# ADC.net
KiCad netlist of a schematic drawn in EAGLE
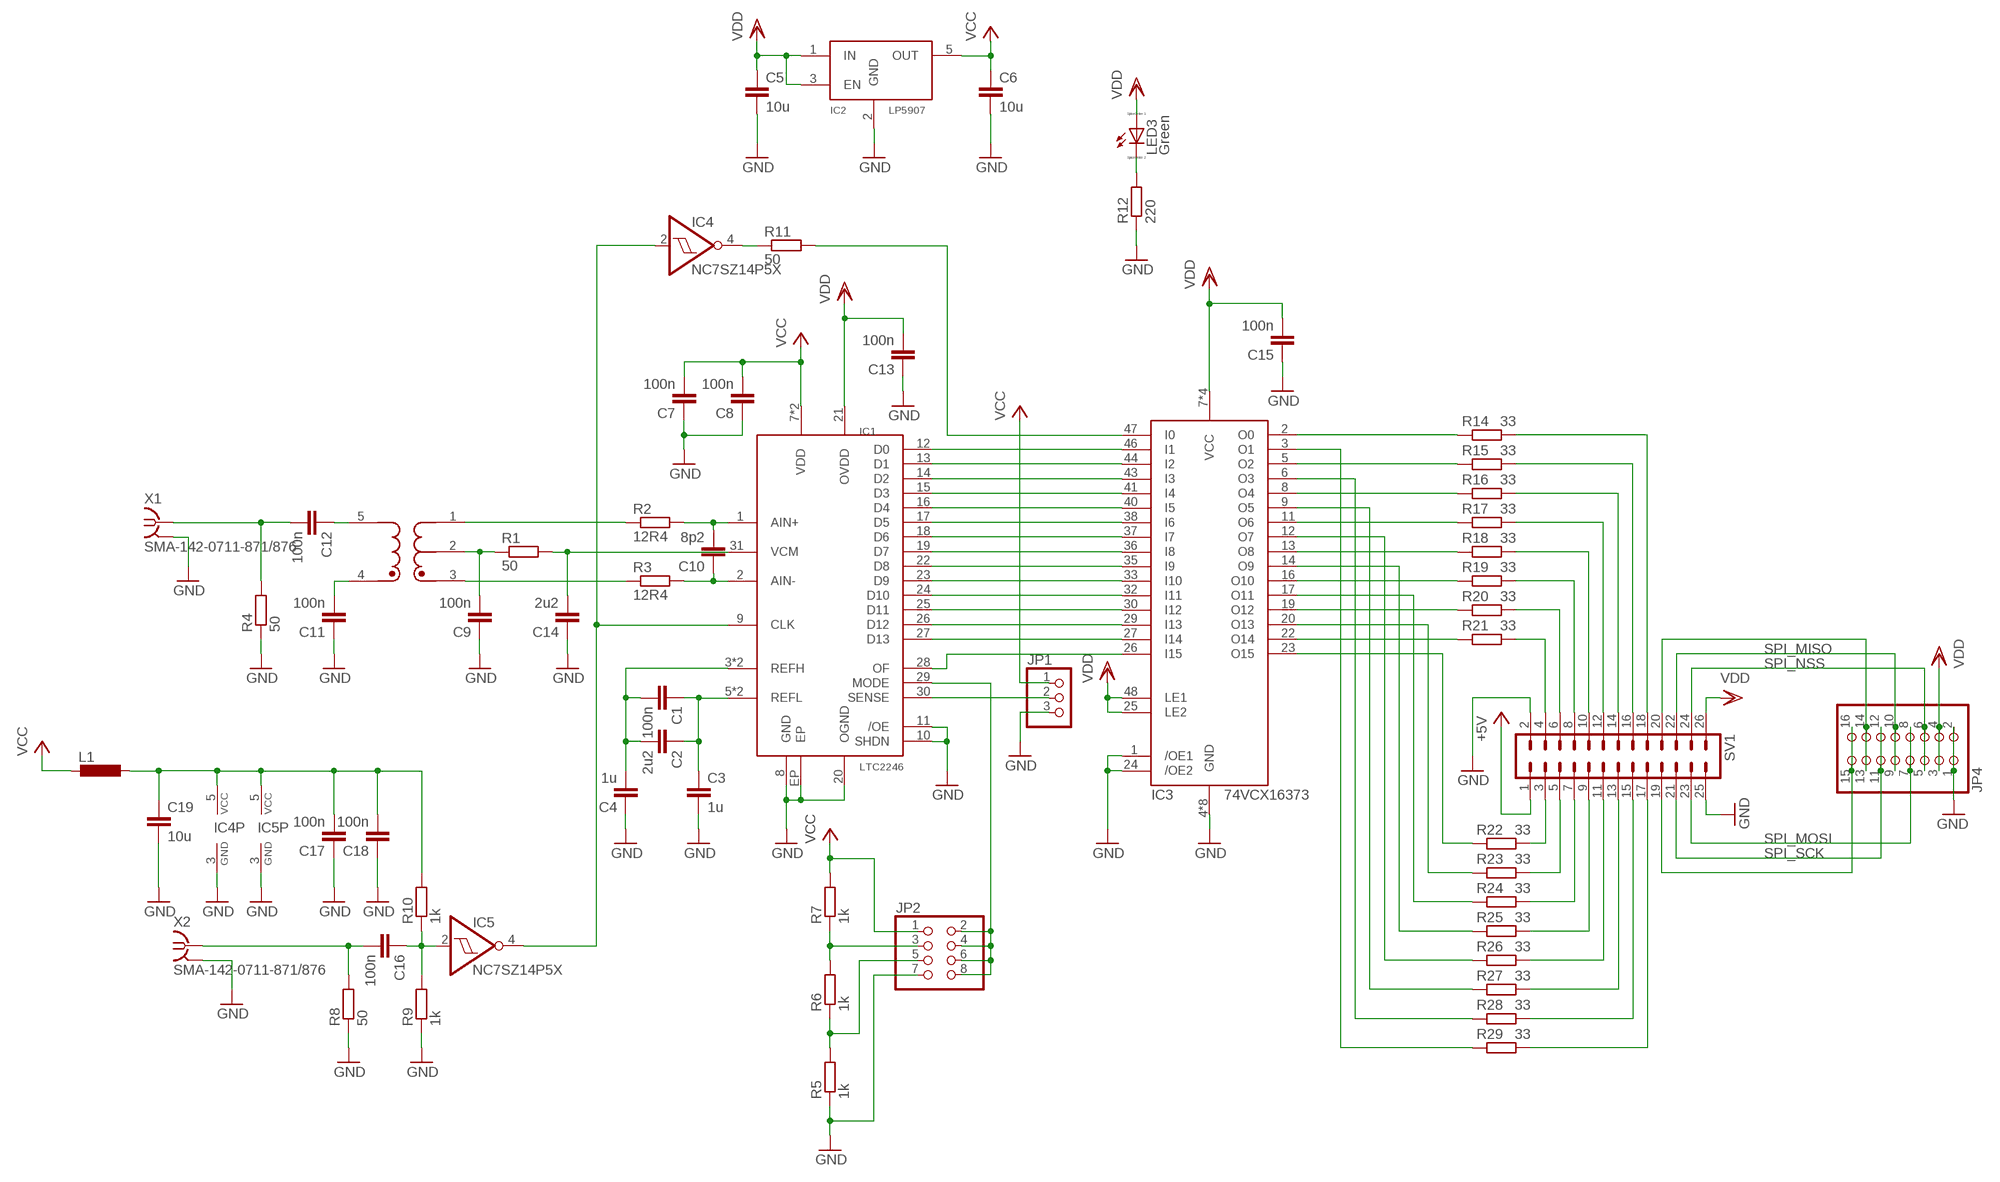
[diagram p0: schematic, sheet 1]

(export (version "E")
  (design (tool "Eeschema 10.0.6"))
  (components
    (comp (ref "B1")
      (value "ETC1-1T")
      (footprint "eagle-import:SM-22")
      (libsource (lib "eagle-import") (part "ETC1-1T"))
    )
    (comp (ref "C1")
      (value "100n")
      (footprint "eagle-import:C0402K")
      (libsource (lib "eagle-import") (part "C-EUC0402K"))
    )
    (comp (ref "C2")
      (value "2u2")
      (footprint "eagle-import:C0603K")
      (libsource (lib "eagle-import") (part "C-EUC0603K"))
    )
    (comp (ref "C3")
      (value "1u")
      (footprint "eagle-import:C0603K")
      (libsource (lib "eagle-import") (part "C-EUC0603K"))
    )
    (comp (ref "C4")
      (value "1u")
      (footprint "eagle-import:C0603K")
      (libsource (lib "eagle-import") (part "C-EUC0603K"))
    )
    (comp (ref "C5")
      (value "10u")
      (footprint "eagle-import:C1206K")
      (libsource (lib "eagle-import") (part "resistor_C-EUC1206K"))
    )
    (comp (ref "C6")
      (value "10u")
      (footprint "eagle-import:C1206K")
      (libsource (lib "eagle-import") (part "resistor_C-EUC1206K"))
    )
    (comp (ref "C7")
      (value "100n")
      (footprint "eagle-import:C0603K")
      (libsource (lib "eagle-import") (part "C-EUC0603K"))
    )
    (comp (ref "C8")
      (value "100n")
      (footprint "eagle-import:C0603K")
      (libsource (lib "eagle-import") (part "C-EUC0603K"))
    )
    (comp (ref "C9")
      (value "100n")
      (footprint "eagle-import:C0603K")
      (libsource (lib "eagle-import") (part "C-EUC0603K"))
    )
    (comp (ref "C10")
      (value "8p2")
      (footprint "eagle-import:C0603K")
      (libsource (lib "eagle-import") (part "C-EUC0603K"))
    )
    (comp (ref "C11")
      (value "100n")
      (footprint "eagle-import:C0603K")
      (libsource (lib "eagle-import") (part "C-EUC0603K"))
    )
    (comp (ref "C12")
      (value "100n")
      (footprint "eagle-import:C0603K")
      (libsource (lib "eagle-import") (part "C-EUC0603K"))
    )
    (comp (ref "C13")
      (value "100n")
      (footprint "eagle-import:C0402K")
      (libsource (lib "eagle-import") (part "C-EUC0402K"))
    )
    (comp (ref "C14")
      (value "2u2")
      (footprint "eagle-import:C0603K")
      (libsource (lib "eagle-import") (part "C-EUC0603K"))
    )
    (comp (ref "C15")
      (value "100n")
      (footprint "eagle-import:C0603K")
      (libsource (lib "eagle-import") (part "C-EUC0603K"))
    )
    (comp (ref "C16")
      (value "100n")
      (footprint "eagle-import:C0603K")
      (libsource (lib "eagle-import") (part "C-EUC0603K"))
    )
    (comp (ref "C17")
      (value "100n")
      (footprint "eagle-import:C0603K")
      (libsource (lib "eagle-import") (part "C-EUC0603K"))
    )
    (comp (ref "C18")
      (value "100n")
      (footprint "eagle-import:C0603K")
      (libsource (lib "eagle-import") (part "C-EUC0603K"))
    )
    (comp (ref "C19")
      (value "10u")
      (footprint "eagle-import:C1206K")
      (libsource (lib "eagle-import") (part "resistor_C-EUC1206K"))
    )
    (comp (ref "IC1")
      (value "LTC2246")
      (footprint "eagle-import:TQFP32-EP")
      (libsource (lib "eagle-import") (part "LTC2246"))
    )
    (comp (ref "IC2")
      (value "LP5907")
      (footprint "eagle-import:SOT23-5L")
      (libsource (lib "eagle-import") (part "LP5907"))
    )
    (comp (ref "IC3")
      (value "74VCX16373")
      (footprint "eagle-import:SOP50P810X120-48")
      (libsource (lib "eagle-import") (part "74VCX16373"))
    )
    (comp (ref "IC4")
      (value "NC7SZ14P5X")
      (footprint "eagle-import:SC70-5")
      (libsource (lib "eagle-import") (part "NC7SZ14P5X"))
    )
    (comp (ref "IC5")
      (value "NC7SZ14P5X")
      (footprint "eagle-import:SC70-5")
      (libsource (lib "eagle-import") (part "NC7SZ14P5X"))
    )
    (comp (ref "JP1")
      (value "PINHD-1X3")
      (footprint "eagle-import:1X03")
      (libsource (lib "eagle-import") (part "PINHD-1X3"))
    )
    (comp (ref "JP2")
      (value "PINHD-2X4")
      (footprint "eagle-import:2X04")
      (libsource (lib "eagle-import") (part "PINHD-2X4"))
    )
    (comp (ref "JP4")
      (value "PINHD-2X8/90")
      (footprint "eagle-import:2X08_90")
      (libsource (lib "eagle-import") (part "PINHD-2X8/90"))
    )
    (comp (ref "L1")
      (value "L-EUL2012C")
      (footprint "eagle-import:L2012C")
      (libsource (lib "eagle-import") (part "L-EUL2012C"))
    )
    (comp (ref "LED3")
      (value "Green")
      (footprint "eagle-import:LED_SML0603")
      (libsource (lib "eagle-import") (part "LED_ESML0603"))
    )
    (comp (ref "R1")
      (value "50")
      (footprint "eagle-import:R0603")
      (libsource (lib "eagle-import") (part "resistor_348_R-EU_R0603"))
    )
    (comp (ref "R2")
      (value "12R4")
      (footprint "eagle-import:R0603")
      (libsource (lib "eagle-import") (part "resistor_348_R-EU_R0603"))
    )
    (comp (ref "R3")
      (value "12R4")
      (footprint "eagle-import:R0603")
      (libsource (lib "eagle-import") (part "resistor_348_R-EU_R0603"))
    )
    (comp (ref "R4")
      (value "50")
      (footprint "eagle-import:R0603")
      (libsource (lib "eagle-import") (part "resistor_348_R-EU_R0603"))
    )
    (comp (ref "R5")
      (value "1k")
      (footprint "eagle-import:R0603")
      (libsource (lib "eagle-import") (part "resistor_348_R-EU_R0603"))
    )
    (comp (ref "R6")
      (value "1k")
      (footprint "eagle-import:R0603")
      (libsource (lib "eagle-import") (part "resistor_348_R-EU_R0603"))
    )
    (comp (ref "R7")
      (value "1k")
      (footprint "eagle-import:R0603")
      (libsource (lib "eagle-import") (part "resistor_348_R-EU_R0603"))
    )
    (comp (ref "R8")
      (value "50")
      (footprint "eagle-import:R0603")
      (libsource (lib "eagle-import") (part "resistor_348_R-EU_R0603"))
    )
    (comp (ref "R9")
      (value "1k")
      (footprint "eagle-import:R0603")
      (libsource (lib "eagle-import") (part "resistor_348_R-EU_R0603"))
    )
    (comp (ref "R10")
      (value "1k")
      (footprint "eagle-import:R0603")
      (libsource (lib "eagle-import") (part "resistor_348_R-EU_R0603"))
    )
    (comp (ref "R11")
      (value "50")
      (footprint "eagle-import:R0603")
      (libsource (lib "eagle-import") (part "resistor_348_R-EU_R0603"))
    )
    (comp (ref "R12")
      (value "220")
      (footprint "eagle-import:R0603")
      (libsource (lib "eagle-import") (part "R-EU_R0603"))
    )
    (comp (ref "R14")
      (value "33")
      (footprint "eagle-import:R0603")
      (libsource (lib "eagle-import") (part "R-EU_R0603"))
    )
    (comp (ref "R15")
      (value "33")
      (footprint "eagle-import:R0603")
      (libsource (lib "eagle-import") (part "R-EU_R0603"))
    )
    (comp (ref "R16")
      (value "33")
      (footprint "eagle-import:R0603")
      (libsource (lib "eagle-import") (part "R-EU_R0603"))
    )
    (comp (ref "R17")
      (value "33")
      (footprint "eagle-import:R0603")
      (libsource (lib "eagle-import") (part "R-EU_R0603"))
    )
    (comp (ref "R18")
      (value "33")
      (footprint "eagle-import:R0603")
      (libsource (lib "eagle-import") (part "R-EU_R0603"))
    )
    (comp (ref "R19")
      (value "33")
      (footprint "eagle-import:R0603")
      (libsource (lib "eagle-import") (part "R-EU_R0603"))
    )
    (comp (ref "R20")
      (value "33")
      (footprint "eagle-import:R0603")
      (libsource (lib "eagle-import") (part "R-EU_R0603"))
    )
    (comp (ref "R21")
      (value "33")
      (footprint "eagle-import:R0603")
      (libsource (lib "eagle-import") (part "R-EU_R0603"))
    )
    (comp (ref "R22")
      (value "33")
      (footprint "eagle-import:R0603")
      (libsource (lib "eagle-import") (part "R-EU_R0603"))
    )
    (comp (ref "R23")
      (value "33")
      (footprint "eagle-import:R0603")
      (libsource (lib "eagle-import") (part "R-EU_R0603"))
    )
    (comp (ref "R24")
      (value "33")
      (footprint "eagle-import:R0603")
      (libsource (lib "eagle-import") (part "R-EU_R0603"))
    )
    (comp (ref "R25")
      (value "33")
      (footprint "eagle-import:R0603")
      (libsource (lib "eagle-import") (part "R-EU_R0603"))
    )
    (comp (ref "R26")
      (value "33")
      (footprint "eagle-import:R0603")
      (libsource (lib "eagle-import") (part "R-EU_R0603"))
    )
    (comp (ref "R27")
      (value "33")
      (footprint "eagle-import:R0603")
      (libsource (lib "eagle-import") (part "R-EU_R0603"))
    )
    (comp (ref "R28")
      (value "33")
      (footprint "eagle-import:R0603")
      (libsource (lib "eagle-import") (part "R-EU_R0603"))
    )
    (comp (ref "R29")
      (value "33")
      (footprint "eagle-import:R0603")
      (libsource (lib "eagle-import") (part "R-EU_R0603"))
    )
    (comp (ref "SV1")
      (value "ML26L")
      (footprint "eagle-import:ML26L")
      (libsource (lib "eagle-import") (part "ML26L"))
    )
    (comp (ref "X1")
      (value "SMA-142-0711-871/876")
      (footprint "eagle-import:J502-ND-142-0711-871_876")
      (fields (field (name "MF") "JOHNSON COMPONENTS") (field (name "MPN") "142-0711-871"))
      (libsource (lib "eagle-import") (part "SMA-142-0711-871/876"))
    )
    (comp (ref "X2")
      (value "SMA-142-0711-871/876")
      (footprint "eagle-import:J502-ND-142-0711-871_876")
      (fields (field (name "MF") "JOHNSON COMPONENTS") (field (name "MPN") "142-0711-871"))
      (libsource (lib "eagle-import") (part "SMA-142-0711-871/876"))
    )
  )
  (nets
    (net (code "1") (name "+5V") (class "Default")
      (node (ref "SV1") (pin "1") (pinfunction "1_1") (pintype "passive"))
    )
    (net (code "2") (name "/SPI_MISO") (class "Default")
      (node (ref "JP4") (pin "10") (pinfunction "10_10") (pintype "passive"))
      (node (ref "JP4") (pin "9") (pinfunction "9_9") (pintype "passive"))
      (node (ref "SV1") (pin "22") (pinfunction "22_22") (pintype "passive"))
    )
    (net (code "3") (name "/SPI_MOSI") (class "Default")
      (node (ref "JP4") (pin "7") (pinfunction "7_7") (pintype "passive"))
      (node (ref "JP4") (pin "8") (pinfunction "8_8") (pintype "passive"))
      (node (ref "SV1") (pin "23") (pinfunction "23_23") (pintype "passive"))
    )
    (net (code "4") (name "/SPI_NSS") (class "Default")
      (node (ref "JP4") (pin "5") (pinfunction "5_5") (pintype "passive"))
      (node (ref "JP4") (pin "6") (pinfunction "6_6") (pintype "passive"))
      (node (ref "SV1") (pin "24") (pinfunction "24_24") (pintype "passive"))
    )
    (net (code "5") (name "/SPI_SCK") (class "Default")
      (node (ref "JP4") (pin "11") (pinfunction "11_11") (pintype "passive"))
      (node (ref "JP4") (pin "12") (pinfunction "12_12") (pintype "passive"))
      (node (ref "SV1") (pin "21") (pinfunction "21_21") (pintype "passive"))
    )
    (net (code "6") (name "GND") (class "Default")
      (node (ref "C11") (pin "1") (pinfunction "1_1") (pintype "passive"))
      (node (ref "C13") (pin "1") (pinfunction "1_1") (pintype "passive"))
      (node (ref "C14") (pin "1") (pinfunction "1_1") (pintype "passive"))
      (node (ref "C15") (pin "1") (pinfunction "1_1") (pintype "passive"))
      (node (ref "C17") (pin "1") (pinfunction "1_1") (pintype "passive"))
      (node (ref "C18") (pin "1") (pinfunction "1_1") (pintype "passive"))
      (node (ref "C19") (pin "2") (pinfunction "2_2") (pintype "passive"))
      (node (ref "C3") (pin "2") (pinfunction "2_2") (pintype "passive"))
      (node (ref "C4") (pin "1") (pinfunction "1_1") (pintype "passive"))
      (node (ref "C5") (pin "2") (pinfunction "2_2") (pintype "passive"))
      (node (ref "C6") (pin "2") (pinfunction "2_2") (pintype "passive"))
      (node (ref "C7") (pin "1") (pinfunction "1_1") (pintype "passive"))
      (node (ref "C8") (pin "1") (pinfunction "1_1") (pintype "passive"))
      (node (ref "C9") (pin "1") (pinfunction "1_1") (pintype "passive"))
      (node (ref "IC1") (pin "10") (pinfunction "SHDN_10") (pintype "bidirectional"))
      (node (ref "IC1") (pin "11") (pinfunction "/OE_11") (pintype "bidirectional"))
      (node (ref "IC1") (pin "20") (pinfunction "OGND_20") (pintype "bidirectional"))
      (node (ref "IC1") (pin "8") (pinfunction "GND_8") (pintype "bidirectional"))
      (node (ref "IC1") (pin "EP") (pinfunction "EP_EP") (pintype "bidirectional"))
      (node (ref "IC2") (pin "2") (pinfunction "GND_2") (pintype "bidirectional"))
      (node (ref "IC3") (pin "1") (pinfunction "/OE1_1") (pintype "bidirectional"))
      (node (ref "IC3") (pin "10") (pinfunction "GND_10") (pintype "bidirectional"))
      (node (ref "IC3") (pin "15") (pinfunction "GND_15") (pintype "bidirectional"))
      (node (ref "IC3") (pin "21") (pinfunction "GND_21") (pintype "bidirectional"))
      (node (ref "IC3") (pin "24") (pinfunction "/OE2_24") (pintype "bidirectional"))
      (node (ref "IC3") (pin "28") (pinfunction "GND_28") (pintype "bidirectional"))
      (node (ref "IC3") (pin "34") (pinfunction "GND_34") (pintype "bidirectional"))
      (node (ref "IC3") (pin "39") (pinfunction "GND_39") (pintype "bidirectional"))
      (node (ref "IC3") (pin "4") (pinfunction "GND_4") (pintype "bidirectional"))
      (node (ref "IC3") (pin "45") (pinfunction "GND_45") (pintype "bidirectional"))
      (node (ref "IC4") (pin "3") (pinfunction "GND_3") (pintype "power_in"))
      (node (ref "IC5") (pin "3") (pinfunction "GND_3") (pintype "power_in"))
      (node (ref "JP1") (pin "3") (pinfunction "3_3") (pintype "passive"))
      (node (ref "JP2") (pin "7") (pinfunction "7_7") (pintype "passive"))
      (node (ref "JP4") (pin "1") (pinfunction "1_1") (pintype "passive"))
      (node (ref "JP4") (pin "2") (pinfunction "2_2") (pintype "passive"))
      (node (ref "R12") (pin "1") (pinfunction "1_1") (pintype "passive"))
      (node (ref "R4") (pin "1") (pinfunction "1_1") (pintype "passive"))
      (node (ref "R5") (pin "1") (pinfunction "1_1") (pintype "passive"))
      (node (ref "R8") (pin "1") (pinfunction "1_1") (pintype "passive"))
      (node (ref "R9") (pin "1") (pinfunction "1_1") (pintype "passive"))
      (node (ref "SV1") (pin "2") (pinfunction "2_2") (pintype "passive"))
      (node (ref "SV1") (pin "25") (pinfunction "25_25") (pintype "passive"))
      (node (ref "X1") (pin "G@1") (pinfunction "2_G@1") (pintype "passive"))
      (node (ref "X1") (pin "G@2") (pinfunction "2_G@2") (pintype "passive"))
      (node (ref "X1") (pin "G@3") (pinfunction "2_G@3") (pintype "passive"))
      (node (ref "X1") (pin "G@4") (pinfunction "2_G@4") (pintype "passive"))
      (node (ref "X2") (pin "G@1") (pinfunction "2_G@1") (pintype "passive"))
      (node (ref "X2") (pin "G@2") (pinfunction "2_G@2") (pintype "passive"))
      (node (ref "X2") (pin "G@3") (pinfunction "2_G@3") (pintype "passive"))
      (node (ref "X2") (pin "G@4") (pinfunction "2_G@4") (pintype "passive"))
    )
    (net (code "7") (name "Net-(B1-PRI)") (class "Default")
      (node (ref "B1") (pin "5") (pinfunction "PRI_5") (pintype "bidirectional"))
      (node (ref "C12") (pin "1") (pinfunction "1_1") (pintype "passive"))
    )
    (net (code "8") (name "Net-(B1-PRI_DOT)") (class "Default")
      (node (ref "B1") (pin "4") (pinfunction "PRI_DOT_4") (pintype "bidirectional"))
      (node (ref "C11") (pin "2") (pinfunction "2_2") (pintype "passive"))
    )
    (net (code "9") (name "Net-(B1-SEC)") (class "Default")
      (node (ref "B1") (pin "1") (pinfunction "SEC_1") (pintype "bidirectional"))
      (node (ref "R2") (pin "1") (pinfunction "1_1") (pintype "passive"))
    )
    (net (code "10") (name "Net-(B1-SEC_CT)") (class "Default")
      (node (ref "B1") (pin "2") (pinfunction "SEC_CT_2") (pintype "bidirectional"))
      (node (ref "C9") (pin "2") (pinfunction "2_2") (pintype "passive"))
      (node (ref "R1") (pin "1") (pinfunction "1_1") (pintype "passive"))
    )
    (net (code "11") (name "Net-(B1-SEC_DOT)") (class "Default")
      (node (ref "B1") (pin "3") (pinfunction "SEC_DOT_3") (pintype "bidirectional"))
      (node (ref "R3") (pin "1") (pinfunction "1_1") (pintype "passive"))
    )
    (net (code "12") (name "Net-(C1-Pad1)") (class "Default")
      (node (ref "C1") (pin "1") (pinfunction "1_1") (pintype "passive"))
      (node (ref "C2") (pin "1") (pinfunction "1_1") (pintype "passive"))
      (node (ref "C3") (pin "1") (pinfunction "1_1") (pintype "passive"))
      (node (ref "IC1") (pin "5") (pinfunction "REFL_5") (pintype "bidirectional"))
      (node (ref "IC1") (pin "6") (pinfunction "REFL_6") (pintype "bidirectional"))
    )
    (net (code "13") (name "Net-(C1-Pad2)") (class "Default")
      (node (ref "C1") (pin "2") (pinfunction "2_2") (pintype "passive"))
      (node (ref "C2") (pin "2") (pinfunction "2_2") (pintype "passive"))
      (node (ref "C4") (pin "2") (pinfunction "2_2") (pintype "passive"))
      (node (ref "IC1") (pin "3") (pinfunction "REFH_3") (pintype "bidirectional"))
      (node (ref "IC1") (pin "4") (pinfunction "REFH_4") (pintype "bidirectional"))
    )
    (net (code "14") (name "Net-(C12-Pad2)") (class "Default")
      (node (ref "C12") (pin "2") (pinfunction "2_2") (pintype "passive"))
      (node (ref "R4") (pin "2") (pinfunction "2_2") (pintype "passive"))
      (node (ref "X1") (pin "1") (pinfunction "1_1") (pintype "passive"))
    )
    (net (code "15") (name "Net-(C16-Pad2)") (class "Default")
      (node (ref "C16") (pin "2") (pinfunction "2_2") (pintype "passive"))
      (node (ref "R8") (pin "2") (pinfunction "2_2") (pintype "passive"))
      (node (ref "X2") (pin "1") (pinfunction "1_1") (pintype "passive"))
    )
    (net (code "16") (name "Net-(IC1-AIN+)") (class "Default")
      (node (ref "C10") (pin "2") (pinfunction "2_2") (pintype "passive"))
      (node (ref "IC1") (pin "1") (pinfunction "AIN+_1") (pintype "bidirectional"))
      (node (ref "R2") (pin "2") (pinfunction "2_2") (pintype "passive"))
    )
    (net (code "17") (name "Net-(IC1-AIN-)") (class "Default")
      (node (ref "C10") (pin "1") (pinfunction "1_1") (pintype "passive"))
      (node (ref "IC1") (pin "2") (pinfunction "AIN-_2") (pintype "bidirectional"))
      (node (ref "R3") (pin "2") (pinfunction "2_2") (pintype "passive"))
    )
    (net (code "18") (name "Net-(IC1-CLK)") (class "Default")
      (node (ref "IC1") (pin "9") (pinfunction "CLK_9") (pintype "bidirectional"))
      (node (ref "IC4") (pin "2") (pinfunction "I_2") (pintype "input"))
      (node (ref "IC5") (pin "4") (pinfunction "O_4") (pintype "output"))
    )
    (net (code "19") (name "Net-(IC1-D0)") (class "Default")
      (node (ref "IC1") (pin "12") (pinfunction "D0_12") (pintype "bidirectional"))
      (node (ref "IC3") (pin "46") (pinfunction "I1_46") (pintype "bidirectional"))
    )
    (net (code "20") (name "Net-(IC1-D1)") (class "Default")
      (node (ref "IC1") (pin "13") (pinfunction "D1_13") (pintype "bidirectional"))
      (node (ref "IC3") (pin "44") (pinfunction "I2_44") (pintype "bidirectional"))
    )
    (net (code "21") (name "Net-(IC1-D2)") (class "Default")
      (node (ref "IC1") (pin "14") (pinfunction "D2_14") (pintype "bidirectional"))
      (node (ref "IC3") (pin "43") (pinfunction "I3_43") (pintype "bidirectional"))
    )
    (net (code "22") (name "Net-(IC1-D3)") (class "Default")
      (node (ref "IC1") (pin "15") (pinfunction "D3_15") (pintype "bidirectional"))
      (node (ref "IC3") (pin "41") (pinfunction "I4_41") (pintype "bidirectional"))
    )
    (net (code "23") (name "Net-(IC1-D4)") (class "Default")
      (node (ref "IC1") (pin "16") (pinfunction "D4_16") (pintype "bidirectional"))
      (node (ref "IC3") (pin "40") (pinfunction "I5_40") (pintype "bidirectional"))
    )
    (net (code "24") (name "Net-(IC1-D5)") (class "Default")
      (node (ref "IC1") (pin "17") (pinfunction "D5_17") (pintype "bidirectional"))
      (node (ref "IC3") (pin "38") (pinfunction "I6_38") (pintype "bidirectional"))
    )
    (net (code "25") (name "Net-(IC1-D6)") (class "Default")
      (node (ref "IC1") (pin "18") (pinfunction "D6_18") (pintype "bidirectional"))
      (node (ref "IC3") (pin "37") (pinfunction "I7_37") (pintype "bidirectional"))
    )
    (net (code "26") (name "Net-(IC1-D7)") (class "Default")
      (node (ref "IC1") (pin "19") (pinfunction "D7_19") (pintype "bidirectional"))
      (node (ref "IC3") (pin "36") (pinfunction "I8_36") (pintype "bidirectional"))
    )
    (net (code "27") (name "Net-(IC1-D8)") (class "Default")
      (node (ref "IC1") (pin "22") (pinfunction "D8_22") (pintype "bidirectional"))
      (node (ref "IC3") (pin "35") (pinfunction "I9_35") (pintype "bidirectional"))
    )
    (net (code "28") (name "Net-(IC1-D9)") (class "Default")
      (node (ref "IC1") (pin "23") (pinfunction "D9_23") (pintype "bidirectional"))
      (node (ref "IC3") (pin "33") (pinfunction "I10_33") (pintype "bidirectional"))
    )
    (net (code "29") (name "Net-(IC1-D10)") (class "Default")
      (node (ref "IC1") (pin "24") (pinfunction "D10_24") (pintype "bidirectional"))
      (node (ref "IC3") (pin "32") (pinfunction "I11_32") (pintype "bidirectional"))
    )
    (net (code "30") (name "Net-(IC1-D11)") (class "Default")
      (node (ref "IC1") (pin "25") (pinfunction "D11_25") (pintype "bidirectional"))
      (node (ref "IC3") (pin "30") (pinfunction "I12_30") (pintype "bidirectional"))
    )
    (net (code "31") (name "Net-(IC1-D12)") (class "Default")
      (node (ref "IC1") (pin "26") (pinfunction "D12_26") (pintype "bidirectional"))
      (node (ref "IC3") (pin "29") (pinfunction "I13_29") (pintype "bidirectional"))
    )
    (net (code "32") (name "Net-(IC1-D13)") (class "Default")
      (node (ref "IC1") (pin "27") (pinfunction "D13_27") (pintype "bidirectional"))
      (node (ref "IC3") (pin "27") (pinfunction "I14_27") (pintype "bidirectional"))
    )
    (net (code "33") (name "Net-(IC1-MODE)") (class "Default")
      (node (ref "IC1") (pin "29") (pinfunction "MODE_29") (pintype "bidirectional"))
      (node (ref "JP2") (pin "2") (pinfunction "2_2") (pintype "passive"))
      (node (ref "JP2") (pin "4") (pinfunction "4_4") (pintype "passive"))
      (node (ref "JP2") (pin "6") (pinfunction "6_6") (pintype "passive"))
      (node (ref "JP2") (pin "8") (pinfunction "8_8") (pintype "passive"))
    )
    (net (code "34") (name "Net-(IC1-OF)") (class "Default")
      (node (ref "IC1") (pin "28") (pinfunction "OF_28") (pintype "bidirectional"))
      (node (ref "IC3") (pin "26") (pinfunction "I15_26") (pintype "bidirectional"))
    )
    (net (code "35") (name "Net-(IC1-SENSE)") (class "Default")
      (node (ref "IC1") (pin "30") (pinfunction "SENSE_30") (pintype "bidirectional"))
      (node (ref "JP1") (pin "2") (pinfunction "2_2") (pintype "passive"))
    )
    (net (code "36") (name "Net-(IC1-VCM)") (class "Default")
      (node (ref "C14") (pin "2") (pinfunction "2_2") (pintype "passive"))
      (node (ref "IC1") (pin "31") (pinfunction "VCM_31") (pintype "bidirectional"))
      (node (ref "R1") (pin "2") (pinfunction "2_2") (pintype "passive"))
    )
    (net (code "37") (name "Net-(IC3-I0)") (class "Default")
      (node (ref "IC3") (pin "47") (pinfunction "I0_47") (pintype "bidirectional"))
      (node (ref "R11") (pin "2") (pinfunction "2_2") (pintype "passive"))
    )
    (net (code "38") (name "Net-(IC3-O0)") (class "Default")
      (node (ref "IC3") (pin "2") (pinfunction "O0_2") (pintype "bidirectional"))
      (node (ref "R14") (pin "1") (pinfunction "1_1") (pintype "passive"))
    )
    (net (code "39") (name "Net-(IC3-O1)") (class "Default")
      (node (ref "IC3") (pin "3") (pinfunction "O1_3") (pintype "bidirectional"))
      (node (ref "R29") (pin "1") (pinfunction "1_1") (pintype "passive"))
    )
    (net (code "40") (name "Net-(IC3-O2)") (class "Default")
      (node (ref "IC3") (pin "5") (pinfunction "O2_5") (pintype "bidirectional"))
      (node (ref "R15") (pin "1") (pinfunction "1_1") (pintype "passive"))
    )
    (net (code "41") (name "Net-(IC3-O3)") (class "Default")
      (node (ref "IC3") (pin "6") (pinfunction "O3_6") (pintype "bidirectional"))
      (node (ref "R28") (pin "1") (pinfunction "1_1") (pintype "passive"))
    )
    (net (code "42") (name "Net-(IC3-O4)") (class "Default")
      (node (ref "IC3") (pin "8") (pinfunction "O4_8") (pintype "bidirectional"))
      (node (ref "R16") (pin "1") (pinfunction "1_1") (pintype "passive"))
    )
    (net (code "43") (name "Net-(IC3-O5)") (class "Default")
      (node (ref "IC3") (pin "9") (pinfunction "O5_9") (pintype "bidirectional"))
      (node (ref "R27") (pin "1") (pinfunction "1_1") (pintype "passive"))
    )
    (net (code "44") (name "Net-(IC3-O6)") (class "Default")
      (node (ref "IC3") (pin "11") (pinfunction "O6_11") (pintype "bidirectional"))
      (node (ref "R17") (pin "1") (pinfunction "1_1") (pintype "passive"))
    )
    (net (code "45") (name "Net-(IC3-O7)") (class "Default")
      (node (ref "IC3") (pin "12") (pinfunction "O7_12") (pintype "bidirectional"))
      (node (ref "R26") (pin "1") (pinfunction "1_1") (pintype "passive"))
    )
    (net (code "46") (name "Net-(IC3-O8)") (class "Default")
      (node (ref "IC3") (pin "13") (pinfunction "O8_13") (pintype "bidirectional"))
      (node (ref "R18") (pin "1") (pinfunction "1_1") (pintype "passive"))
    )
    (net (code "47") (name "Net-(IC3-O9)") (class "Default")
      (node (ref "IC3") (pin "14") (pinfunction "O9_14") (pintype "bidirectional"))
      (node (ref "R25") (pin "1") (pinfunction "1_1") (pintype "passive"))
    )
    (net (code "48") (name "Net-(IC3-O10)") (class "Default")
      (node (ref "IC3") (pin "16") (pinfunction "O10_16") (pintype "bidirectional"))
      (node (ref "R19") (pin "1") (pinfunction "1_1") (pintype "passive"))
    )
    (net (code "49") (name "Net-(IC3-O11)") (class "Default")
      (node (ref "IC3") (pin "17") (pinfunction "O11_17") (pintype "bidirectional"))
      (node (ref "R24") (pin "1") (pinfunction "1_1") (pintype "passive"))
    )
    (net (code "50") (name "Net-(IC3-O12)") (class "Default")
      (node (ref "IC3") (pin "19") (pinfunction "O12_19") (pintype "bidirectional"))
      (node (ref "R20") (pin "1") (pinfunction "1_1") (pintype "passive"))
    )
    (net (code "51") (name "Net-(IC3-O13)") (class "Default")
      (node (ref "IC3") (pin "20") (pinfunction "O13_20") (pintype "bidirectional"))
      (node (ref "R23") (pin "1") (pinfunction "1_1") (pintype "passive"))
    )
    (net (code "52") (name "Net-(IC3-O14)") (class "Default")
      (node (ref "IC3") (pin "22") (pinfunction "O14_22") (pintype "bidirectional"))
      (node (ref "R21") (pin "1") (pinfunction "1_1") (pintype "passive"))
    )
    (net (code "53") (name "Net-(IC3-O15)") (class "Default")
      (node (ref "IC3") (pin "23") (pinfunction "O15_23") (pintype "bidirectional"))
      (node (ref "R22") (pin "1") (pinfunction "1_1") (pintype "passive"))
    )
    (net (code "54") (name "Net-(IC4A-O)") (class "Default")
      (node (ref "IC4") (pin "4") (pinfunction "O_4") (pintype "output"))
      (node (ref "R11") (pin "1") (pinfunction "1_1") (pintype "passive"))
    )
    (net (code "55") (name "Net-(IC4B-VCC)") (class "Default")
      (node (ref "C17") (pin "2") (pinfunction "2_2") (pintype "passive"))
      (node (ref "C18") (pin "2") (pinfunction "2_2") (pintype "passive"))
      (node (ref "C19") (pin "1") (pinfunction "1_1") (pintype "passive"))
      (node (ref "IC4") (pin "5") (pinfunction "VCC_5") (pintype "power_in"))
      (node (ref "IC5") (pin "5") (pinfunction "VCC_5") (pintype "power_in"))
      (node (ref "L1") (pin "1") (pinfunction "1_1") (pintype "passive"))
      (node (ref "R10") (pin "2") (pinfunction "2_2") (pintype "passive"))
    )
    (net (code "56") (name "Net-(IC5A-I)") (class "Default")
      (node (ref "C16") (pin "1") (pinfunction "1_1") (pintype "passive"))
      (node (ref "IC5") (pin "2") (pinfunction "I_2") (pintype "input"))
      (node (ref "R10") (pin "1") (pinfunction "1_1") (pintype "passive"))
      (node (ref "R9") (pin "2") (pinfunction "2_2") (pintype "passive"))
    )
    (net (code "57") (name "Net-(JP2-Pad3)") (class "Default")
      (node (ref "JP2") (pin "3") (pinfunction "3_3") (pintype "passive"))
      (node (ref "R6") (pin "2") (pinfunction "2_2") (pintype "passive"))
      (node (ref "R7") (pin "1") (pinfunction "1_1") (pintype "passive"))
    )
    (net (code "58") (name "Net-(JP2-Pad5)") (class "Default")
      (node (ref "JP2") (pin "5") (pinfunction "5_5") (pintype "passive"))
      (node (ref "R5") (pin "2") (pinfunction "2_2") (pintype "passive"))
      (node (ref "R6") (pin "1") (pinfunction "1_1") (pintype "passive"))
    )
    (net (code "59") (name "Net-(JP4-Pad13)") (class "Default")
      (node (ref "JP4") (pin "13") (pinfunction "13_13") (pintype "passive"))
      (node (ref "JP4") (pin "14") (pinfunction "14_14") (pintype "passive"))
      (node (ref "SV1") (pin "20") (pinfunction "20_20") (pintype "passive"))
    )
    (net (code "60") (name "Net-(JP4-Pad15)") (class "Default")
      (node (ref "JP4") (pin "15") (pinfunction "15_15") (pintype "passive"))
      (node (ref "JP4") (pin "16") (pinfunction "16_16") (pintype "passive"))
      (node (ref "SV1") (pin "19") (pinfunction "19_19") (pintype "passive"))
    )
    (net (code "61") (name "Net-(LED3-PadC)") (class "Default")
      (node (ref "LED3") (pin "C") (pinfunction "C_C") (pintype "passive"))
      (node (ref "R12") (pin "2") (pinfunction "2_2") (pintype "passive"))
    )
    (net (code "62") (name "Net-(R14-Pad2)") (class "Default")
      (node (ref "R14") (pin "2") (pinfunction "2_2") (pintype "passive"))
      (node (ref "SV1") (pin "18") (pinfunction "18_18") (pintype "passive"))
    )
    (net (code "63") (name "Net-(R15-Pad2)") (class "Default")
      (node (ref "R15") (pin "2") (pinfunction "2_2") (pintype "passive"))
      (node (ref "SV1") (pin "16") (pinfunction "16_16") (pintype "passive"))
    )
    (net (code "64") (name "Net-(R16-Pad2)") (class "Default")
      (node (ref "R16") (pin "2") (pinfunction "2_2") (pintype "passive"))
      (node (ref "SV1") (pin "14") (pinfunction "14_14") (pintype "passive"))
    )
    (net (code "65") (name "Net-(R17-Pad2)") (class "Default")
      (node (ref "R17") (pin "2") (pinfunction "2_2") (pintype "passive"))
      (node (ref "SV1") (pin "12") (pinfunction "12_12") (pintype "passive"))
    )
    (net (code "66") (name "Net-(R18-Pad2)") (class "Default")
      (node (ref "R18") (pin "2") (pinfunction "2_2") (pintype "passive"))
      (node (ref "SV1") (pin "10") (pinfunction "10_10") (pintype "passive"))
    )
    (net (code "67") (name "Net-(R19-Pad2)") (class "Default")
      (node (ref "R19") (pin "2") (pinfunction "2_2") (pintype "passive"))
      (node (ref "SV1") (pin "8") (pinfunction "8_8") (pintype "passive"))
    )
    (net (code "68") (name "Net-(R20-Pad2)") (class "Default")
      (node (ref "R20") (pin "2") (pinfunction "2_2") (pintype "passive"))
      (node (ref "SV1") (pin "6") (pinfunction "6_6") (pintype "passive"))
    )
    (net (code "69") (name "Net-(R21-Pad2)") (class "Default")
      (node (ref "R21") (pin "2") (pinfunction "2_2") (pintype "passive"))
      (node (ref "SV1") (pin "4") (pinfunction "4_4") (pintype "passive"))
    )
    (net (code "70") (name "Net-(R22-Pad2)") (class "Default")
      (node (ref "R22") (pin "2") (pinfunction "2_2") (pintype "passive"))
      (node (ref "SV1") (pin "3") (pinfunction "3_3") (pintype "passive"))
    )
    (net (code "71") (name "Net-(R23-Pad2)") (class "Default")
      (node (ref "R23") (pin "2") (pinfunction "2_2") (pintype "passive"))
      (node (ref "SV1") (pin "5") (pinfunction "5_5") (pintype "passive"))
    )
    (net (code "72") (name "Net-(R24-Pad2)") (class "Default")
      (node (ref "R24") (pin "2") (pinfunction "2_2") (pintype "passive"))
      (node (ref "SV1") (pin "7") (pinfunction "7_7") (pintype "passive"))
    )
    (net (code "73") (name "Net-(R25-Pad2)") (class "Default")
      (node (ref "R25") (pin "2") (pinfunction "2_2") (pintype "passive"))
      (node (ref "SV1") (pin "9") (pinfunction "9_9") (pintype "passive"))
    )
    (net (code "74") (name "Net-(R26-Pad2)") (class "Default")
      (node (ref "R26") (pin "2") (pinfunction "2_2") (pintype "passive"))
      (node (ref "SV1") (pin "11") (pinfunction "11_11") (pintype "passive"))
    )
    (net (code "75") (name "Net-(R27-Pad2)") (class "Default")
      (node (ref "R27") (pin "2") (pinfunction "2_2") (pintype "passive"))
      (node (ref "SV1") (pin "13") (pinfunction "13_13") (pintype "passive"))
    )
    (net (code "76") (name "Net-(R28-Pad2)") (class "Default")
      (node (ref "R28") (pin "2") (pinfunction "2_2") (pintype "passive"))
      (node (ref "SV1") (pin "15") (pinfunction "15_15") (pintype "passive"))
    )
    (net (code "77") (name "Net-(R29-Pad2)") (class "Default")
      (node (ref "R29") (pin "2") (pinfunction "2_2") (pintype "passive"))
      (node (ref "SV1") (pin "17") (pinfunction "17_17") (pintype "passive"))
    )
    (net (code "78") (name "VCC") (class "Default")
      (node (ref "C6") (pin "1") (pinfunction "1_1") (pintype "passive"))
      (node (ref "C7") (pin "2") (pinfunction "2_2") (pintype "passive"))
      (node (ref "C8") (pin "2") (pinfunction "2_2") (pintype "passive"))
      (node (ref "IC1") (pin "32") (pinfunction "VDD_32") (pintype "bidirectional"))
      (node (ref "IC1") (pin "7") (pinfunction "VDD_7") (pintype "bidirectional"))
      (node (ref "IC2") (pin "5") (pinfunction "OUT_5") (pintype "bidirectional"))
      (node (ref "JP1") (pin "1") (pinfunction "1_1") (pintype "passive"))
      (node (ref "JP2") (pin "1") (pinfunction "1_1") (pintype "passive"))
      (node (ref "L1") (pin "2") (pinfunction "2_2") (pintype "passive"))
      (node (ref "R7") (pin "2") (pinfunction "2_2") (pintype "passive"))
    )
    (net (code "79") (name "VDD") (class "Default")
      (node (ref "C13") (pin "2") (pinfunction "2_2") (pintype "passive"))
      (node (ref "C15") (pin "2") (pinfunction "2_2") (pintype "passive"))
      (node (ref "C5") (pin "1") (pinfunction "1_1") (pintype "passive"))
      (node (ref "IC1") (pin "21") (pinfunction "OVDD_21") (pintype "bidirectional"))
      (node (ref "IC2") (pin "1") (pinfunction "IN_1") (pintype "bidirectional"))
      (node (ref "IC2") (pin "3") (pinfunction "EN_3") (pintype "bidirectional"))
      (node (ref "IC3") (pin "18") (pinfunction "VCC_18") (pintype "bidirectional"))
      (node (ref "IC3") (pin "25") (pinfunction "LE2_25") (pintype "bidirectional"))
      (node (ref "IC3") (pin "31") (pinfunction "VCC_31") (pintype "bidirectional"))
      (node (ref "IC3") (pin "42") (pinfunction "VCC_42") (pintype "bidirectional"))
      (node (ref "IC3") (pin "48") (pinfunction "LE1_48") (pintype "bidirectional"))
      (node (ref "IC3") (pin "7") (pinfunction "VCC_7") (pintype "bidirectional"))
      (node (ref "JP4") (pin "3") (pinfunction "3_3") (pintype "passive"))
      (node (ref "JP4") (pin "4") (pinfunction "4_4") (pintype "passive"))
      (node (ref "LED3") (pin "A") (pinfunction "A_A") (pintype "passive"))
      (node (ref "SV1") (pin "26") (pinfunction "26_26") (pintype "passive"))
    )
  )
)
